# solar_panel_12v.net
KiCad netlist of a schematic drawn in EasyEDA Pro
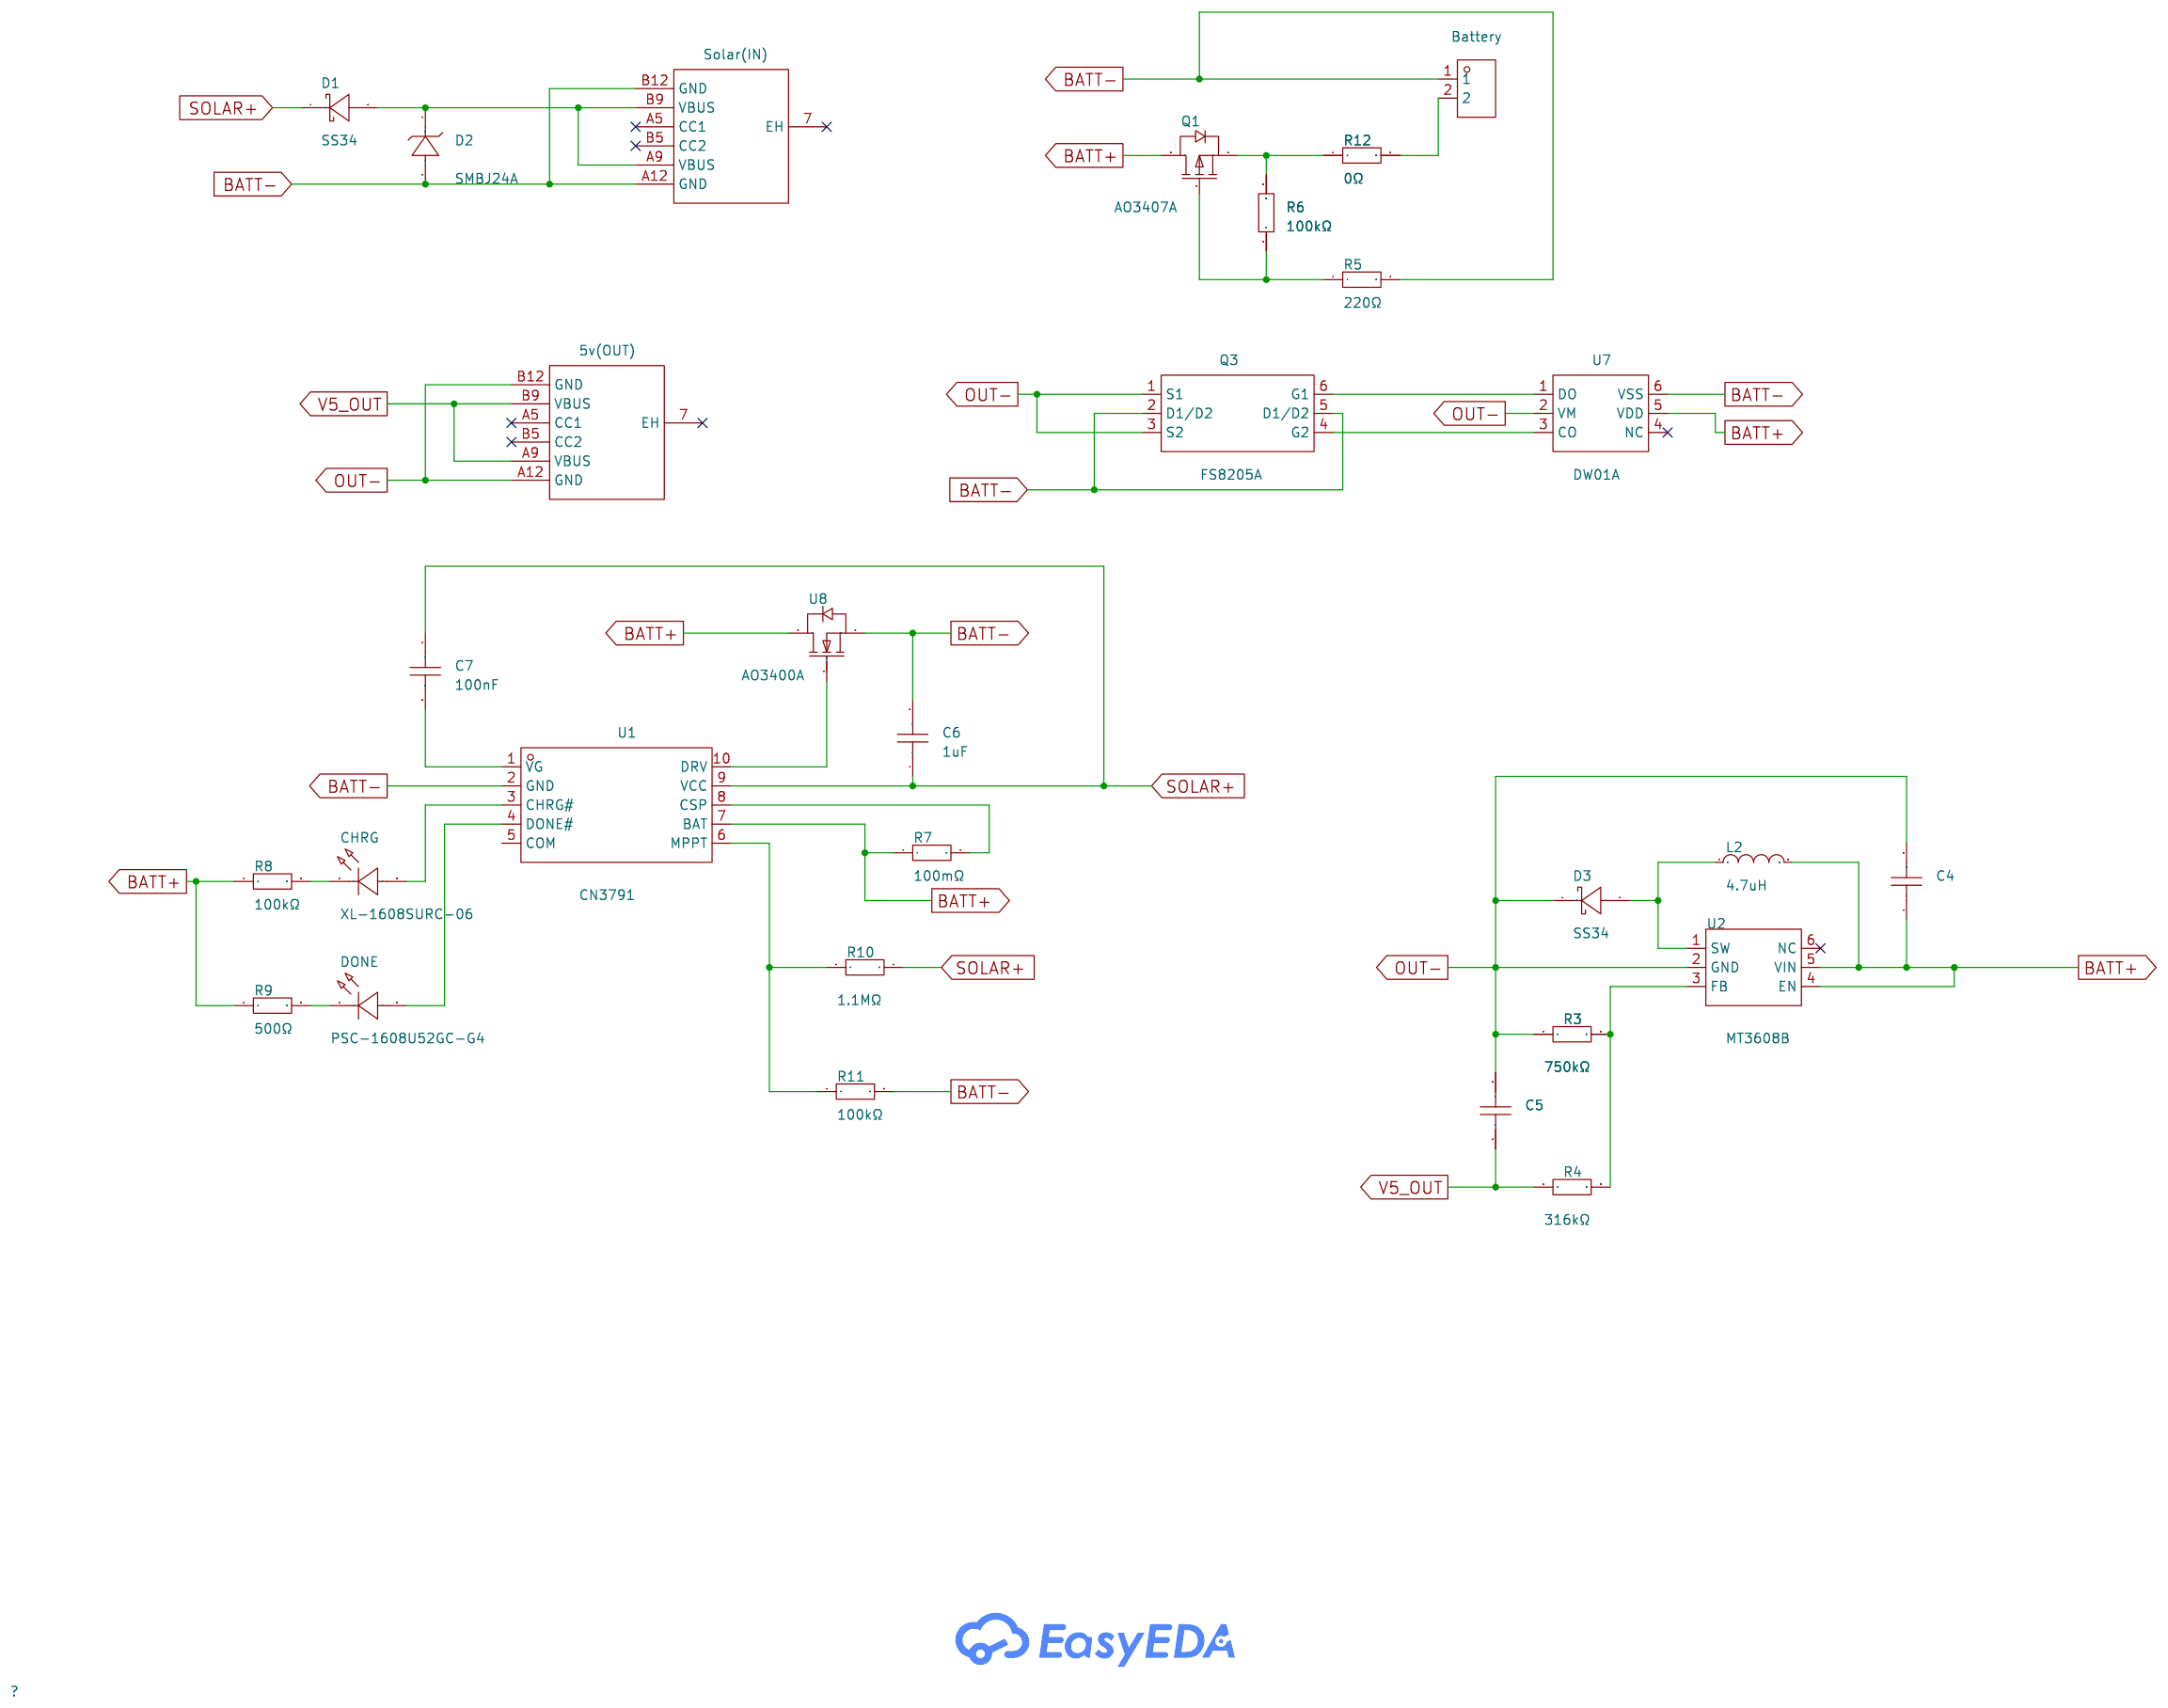
[diagram p0: schematic sheet]

(export (version "E")
  (design (tool "Eeschema 10.0.6"))
  (components
    (comp (ref "5v(OUT)")
      (value "TYPE-C 6P")
      (footprint "easyedapro:TYPE-C-SMD_TYPE-C-6P_1")
      (fields (field (name "Manufacturer") "SHOU HAN(首韩)"))
      (libsource (lib "easyedapro") (part "TYPE-C 6P"))
    )
    (comp (ref "Battery") (value "S2B-PH-SM4-TB(LF)(SN)") (libsource (lib "easyedapro") (part "B2B-PH-KL")))
    (comp (ref "C4")
      (value "10uF")
      (footprint "easyedapro:C0603")
      (description "Capacitance:10uF Tolerance:±20% Tolerance:±20% Voltage Rating:6.3V Temperature Coefficient:X5R")
      (fields (field (name "Manufacturer Part") "C0603B106M007T") (field (name "Manufacturer") "IHHEC(禾伸堂)"))
      (libsource (lib "easyedapro") (part "CAP"))
    )
    (comp (ref "C5")
      (value "10uF")
      (footprint "easyedapro:C0603")
      (description "Capacitance:10uF Tolerance:±20% Tolerance:±20% Voltage Rating:6.3V Temperature Coefficient:X5R")
      (fields (field (name "Manufacturer Part") "C0603B106M007T") (field (name "Manufacturer") "IHHEC(禾伸堂)"))
      (libsource (lib "easyedapro") (part "CAP"))
    )
    (comp (ref "C6")
      (value "1uF")
      (footprint "easyedapro:C0603")
      (description "Capacitance:1uF Tolerance:±10% Tolerance:±10% Voltage Rating:25V Temperature Coefficient:X7R")
      (fields (field (name "Manufacturer Part") "C0603X105K025T") (field (name "Manufacturer") "IHHEC(禾伸堂)"))
      (libsource (lib "easyedapro") (part "CAP"))
    )
    (comp (ref "C7")
      (value "100nF")
      (footprint "easyedapro:C0603")
      (description "Capacitance:100nF Tolerance:±10% Tolerance:±10% Voltage Rating:100V Temperature Coefficient:X7R")
      (fields
        (field (name "Manufacturer Part") "CC0603KRX7R0BB104")
        (field (name "Manufacturer") "YAGEO(国巨)")
      )
      (libsource (lib "easyedapro") (part "CAP"))
    )
    (comp (ref "CHRG")
      (value "XL-1608SURC-06")
      (footprint "easyedapro:LED0603-RD_RED")
      (fields (field (name "Manufacturer") "XINGLIGHT(成兴光)"))
      (libsource (lib "easyedapro") (part "XL-1608SURC-06"))
    )
    (comp (ref "D1")
      (value "SS34")
      (footprint "easyedapro:SMA_L4.3-W2.6-LS5.1-RD")
      (fields (field (name "Manufacturer") "Hangyu(航昱微)"))
      (libsource (lib "easyedapro") (part "SS34_C52023881"))
    )
    (comp (ref "D2")
      (value "SMBJ24A")
      (footprint "easyedapro:SMB_L4.6-W3.6-LS5.3-RD")
      (fields (field (name "Manufacturer") "KUU"))
      (libsource (lib "easyedapro") (part "SMBJ24A_C5343588"))
    )
    (comp (ref "D3")
      (value "SS34")
      (footprint "easyedapro:SMA_L4.3-W2.6-LS5.1-RD")
      (fields (field (name "Manufacturer") "Hangyu(航昱微)"))
      (libsource (lib "easyedapro") (part "SS34_C52023881"))
    )
    (comp (ref "DONE")
      (value "PSC-1608U52GC-G4")
      (footprint "easyedapro:LED0603-RD_GREEN")
      (fields (field (name "Manufacturer") "HONGLITRONIC(鸿利光电)"))
      (libsource (lib "easyedapro") (part "PSC-1608U52GC-G4"))
    )
    (comp (ref "L2")
      (value "4.7uH")
      (footprint "easyedapro:L0805")
      (fields
        (field (name "Manufacturer Part") "CPY201209T-4R7M-NP")
        (field (name "Manufacturer") "Chilisin(奇力新)")
      )
      (libsource (lib "easyedapro") (part "CPY201209T-4R7M-NP"))
    )
    (comp (ref "Q1")
      (value "AO3407A")
      (footprint "easyedapro:SOT-23_L2.9-W1.3-P1.90-LS2.4-BR")
      (fields (field (name "Manufacturer") "UMW(友台半导体)"))
      (libsource (lib "easyedapro") (part "AO3407A_C347478"))
    )
    (comp (ref "Q3")
      (value "FS8205A")
      (footprint "easyedapro:SOT-23-6_L2.9-W1.6-P0.95-LS2.8-BR")
      (fields (field (name "Manufacturer") "FUXINSEMI(富芯森美)"))
      (libsource (lib "easyedapro") (part "FS8205A_C908265"))
    )
    (comp (ref "R3")
      (value "750kΩ")
      (footprint "easyedapro:R0603")
      (fields (field (name "Manufacturer Part") "CR0603FA7503G") (field (name "Manufacturer") "LIZ(丽智电子)"))
      (libsource (lib "easyedapro") (part "Res"))
    )
    (comp (ref "R4")
      (value "316kΩ")
      (footprint "easyedapro:R0603")
      (fields (field (name "Manufacturer Part") "FRC0603F3163TS") (field (name "Manufacturer") "FOJAN(富捷)"))
      (libsource (lib "easyedapro") (part "Res"))
    )
    (comp (ref "R5")
      (value "220Ω")
      (footprint "easyedapro:R0603")
      (fields (field (name "Manufacturer Part") "SCR0603J220R") (field (name "Manufacturer") "VO(翔胜)"))
      (libsource (lib "easyedapro") (part "Res"))
    )
    (comp (ref "R6")
      (value "100kΩ")
      (footprint "easyedapro:R0603")
      (fields (field (name "Manufacturer Part") "FCR0603F100K") (field (name "Manufacturer") "VO(翔胜)"))
      (libsource (lib "easyedapro") (part "Res"))
    )
    (comp (ref "R7")
      (value "100mΩ")
      (footprint "easyedapro:R0603")
      (fields (field (name "Manufacturer Part") "FRM121WFR100TM") (field (name "Manufacturer") "FOJAN(富捷)"))
      (libsource (lib "easyedapro") (part "Res"))
    )
    (comp (ref "R8")
      (value "100kΩ")
      (footprint "easyedapro:R0603")
      (fields (field (name "Manufacturer Part") "FCR0603F100K") (field (name "Manufacturer") "VO(翔胜)"))
      (libsource (lib "easyedapro") (part "Res"))
    )
    (comp (ref "R9")
      (value "500Ω")
      (footprint "easyedapro:R0603")
      (fields (field (name "Manufacturer Part") "ARG05FTC5000") (field (name "Manufacturer") "Viking(光颉)"))
      (libsource (lib "easyedapro") (part "Res"))
    )
    (comp (ref "R10")
      (value "1.1MΩ")
      (footprint "easyedapro:R0603")
      (fields (field (name "Manufacturer Part") "FRC0603J115TS") (field (name "Manufacturer") "FOJAN(富捷)"))
      (libsource (lib "easyedapro") (part "Res"))
    )
    (comp (ref "R11")
      (value "100kΩ")
      (footprint "easyedapro:R0603")
      (fields
        (field (name "Manufacturer Part") "CR0603J100KP05Z")
        (field (name "Manufacturer") "EVER OHMS(天二科技)")
      )
      (libsource (lib "easyedapro") (part "Res"))
    )
    (comp (ref "R12")
      (value "0Ω")
      (footprint "easyedapro:R0603")
      (fields (field (name "Manufacturer Part") "FRC1812P000 TS") (field (name "Manufacturer") "FOJAN(富捷)"))
      (libsource (lib "easyedapro") (part "Res"))
    )
    (comp (ref "Solar(IN)")
      (value "TYPE-C 6P")
      (footprint "easyedapro:TYPE-C-SMD_TYPE-C-6P_1")
      (fields (field (name "Manufacturer") "SHOU HAN(首韩)"))
      (libsource (lib "easyedapro") (part "TYPE-C 6P"))
    )
    (comp (ref "U1")
      (value "CN3791")
      (footprint "easyedapro:SSOP-10_L4.9-W3.9-P1.00-LS6.0-BL")
      (fields (field (name "Manufacturer") "CONSONANCE(上海如韵)"))
      (libsource (lib "easyedapro") (part "CN3791"))
    )
    (comp (ref "U2")
      (value "MT3608B")
      (footprint "easyedapro:SOT-23-6_L2.9-W1.6-P0.95-LS2.8-BR")
      (fields (field (name "Manufacturer") "西安航天民芯"))
      (libsource (lib "easyedapro") (part "MT3608B"))
    )
    (comp (ref "U7")
      (value "DW01A")
      (footprint "easyedapro:SOT-23-6_L2.9-W1.6-P0.95-LS2.9-BL")
      (fields (field (name "Manufacturer") "Slkor(萨科微)"))
      (libsource (lib "easyedapro") (part "DW01A_C42380662"))
    )
    (comp (ref "U8")
      (value "AO3400A")
      (footprint "easyedapro:SOT-23-3_L2.9-W1.3-P1.90-LS2.4-BR")
      (fields (field (name "Manufacturer") "YONGYUTAI(永裕泰)"))
      (libsource (lib "easyedapro") (part "AO3400A_C49195711"))
    )
  )
  (nets
    (net (code "1") (name "BATT+") (class "Default")
      (node (ref "C4") (pin "1") (pinfunction "1_1") (pintype "input"))
      (node (ref "L2") (pin "2") (pinfunction "2_2") (pintype "unspecified"))
      (node (ref "Q1") (pin "3") (pinfunction "D_3") (pintype "unspecified"))
      (node (ref "R7") (pin "1") (pinfunction "1_1") (pintype "input"))
      (node (ref "R8") (pin "1") (pinfunction "1_1") (pintype "input"))
      (node (ref "R9") (pin "1") (pinfunction "1_1") (pintype "input"))
      (node (ref "U1") (pin "7") (pinfunction "BAT_7") (pintype "unspecified"))
      (node (ref "U2") (pin "4") (pinfunction "EN_4") (pintype "unspecified"))
      (node (ref "U2") (pin "5") (pinfunction "VIN_5") (pintype "unspecified"))
      (node (ref "U7") (pin "5") (pinfunction "VDD_5") (pintype "unspecified"))
      (node (ref "U8") (pin "3") (pinfunction "D_3") (pintype "unspecified"))
    )
    (net (code "2") (name "BATT-") (class "Default")
      (node (ref "Battery") (pin "1") (pinfunction "1_1") (pintype "unspecified"))
      (node (ref "C6") (pin "2") (pinfunction "2_2") (pintype "input"))
      (node (ref "D2") (pin "2") (pinfunction "A_2") (pintype "unspecified"))
      (node (ref "Q3") (pin "2") (pinfunction "D1/D2_2") (pintype "unspecified"))
      (node (ref "Q3") (pin "5") (pinfunction "D1/D2_5") (pintype "unspecified"))
      (node (ref "R11") (pin "2") (pinfunction "2_2") (pintype "input"))
      (node (ref "R5") (pin "2") (pinfunction "2_2") (pintype "input"))
      (node (ref "Solar(IN)") (pin "A12") (pinfunction "GND_A12") (pintype "unspecified"))
      (node (ref "Solar(IN)") (pin "B12") (pinfunction "GND_B12") (pintype "unspecified"))
      (node (ref "U1") (pin "2") (pinfunction "GND_2") (pintype "unspecified"))
      (node (ref "U7") (pin "6") (pinfunction "VSS_6") (pintype "unspecified"))
      (node (ref "U8") (pin "2") (pinfunction "S_2") (pintype "unspecified"))
    )
    (net (code "3") (name "Net-(Battery-Pad2)") (class "Default")
      (node (ref "Battery") (pin "2") (pinfunction "2_2") (pintype "unspecified"))
      (node (ref "R12") (pin "2") (pinfunction "2_2") (pintype "input"))
    )
    (net (code "4") (name "Net-(CHRG-A)") (class "Default")
      (node (ref "CHRG") (pin "2") (pinfunction "A_2") (pintype "unspecified"))
      (node (ref "U1") (pin "3") (pinfunction "CHRG#_3") (pintype "unspecified"))
    )
    (net (code "5") (name "Net-(CHRG-K)") (class "Default")
      (node (ref "CHRG") (pin "1") (pinfunction "K_1") (pintype "unspecified"))
      (node (ref "R8") (pin "2") (pinfunction "2_2") (pintype "input"))
    )
    (net (code "6") (name "Net-(D1-A)") (class "Default")
      (node (ref "D1") (pin "2") (pinfunction "A_2") (pintype "unspecified"))
      (node (ref "D2") (pin "1") (pinfunction "C_1") (pintype "unspecified"))
      (node (ref "Solar(IN)") (pin "A9") (pinfunction "VBUS_A9") (pintype "unspecified"))
      (node (ref "Solar(IN)") (pin "B9") (pinfunction "VBUS_B9") (pintype "unspecified"))
    )
    (net (code "7") (name "Net-(D3-A)") (class "Default")
      (node (ref "D3") (pin "2") (pinfunction "A_2") (pintype "unspecified"))
      (node (ref "L2") (pin "1") (pinfunction "1_1") (pintype "unspecified"))
      (node (ref "U2") (pin "1") (pinfunction "SW_1") (pintype "unspecified"))
    )
    (net (code "8") (name "Net-(DONE-A)") (class "Default")
      (node (ref "DONE") (pin "2") (pinfunction "A_2") (pintype "unspecified"))
      (node (ref "U1") (pin "4") (pinfunction "DONE#_4") (pintype "unspecified"))
    )
    (net (code "9") (name "Net-(DONE-K)") (class "Default")
      (node (ref "DONE") (pin "1") (pinfunction "K_1") (pintype "unspecified"))
      (node (ref "R9") (pin "2") (pinfunction "2_2") (pintype "input"))
    )
    (net (code "10") (name "Net-(Q1-G)") (class "Default")
      (node (ref "Q1") (pin "1") (pinfunction "G_1") (pintype "unspecified"))
      (node (ref "R5") (pin "1") (pinfunction "1_1") (pintype "input"))
      (node (ref "R6") (pin "1") (pinfunction "1_1") (pintype "input"))
    )
    (net (code "11") (name "Net-(Q1-S)") (class "Default")
      (node (ref "Q1") (pin "2") (pinfunction "S_2") (pintype "unspecified"))
      (node (ref "R12") (pin "1") (pinfunction "1_1") (pintype "input"))
      (node (ref "R6") (pin "2") (pinfunction "2_2") (pintype "input"))
    )
    (net (code "12") (name "Net-(Q3-G1)") (class "Default")
      (node (ref "Q3") (pin "6") (pinfunction "G1_6") (pintype "unspecified"))
      (node (ref "U7") (pin "1") (pinfunction "DO_1") (pintype "unspecified"))
    )
    (net (code "13") (name "Net-(Q3-G2)") (class "Default")
      (node (ref "Q3") (pin "4") (pinfunction "G2_4") (pintype "unspecified"))
      (node (ref "U7") (pin "3") (pinfunction "CO_3") (pintype "unspecified"))
    )
    (net (code "14") (name "Net-(U1-CSP)") (class "Default")
      (node (ref "R7") (pin "2") (pinfunction "2_2") (pintype "input"))
      (node (ref "U1") (pin "8") (pinfunction "CSP_8") (pintype "unspecified"))
    )
    (net (code "15") (name "Net-(U1-DRV)") (class "Default")
      (node (ref "U1") (pin "10") (pinfunction "DRV_10") (pintype "unspecified"))
      (node (ref "U8") (pin "1") (pinfunction "G_1") (pintype "unspecified"))
    )
    (net (code "16") (name "Net-(U1-MPPT)") (class "Default")
      (node (ref "R10") (pin "1") (pinfunction "1_1") (pintype "input"))
      (node (ref "R11") (pin "1") (pinfunction "1_1") (pintype "input"))
      (node (ref "U1") (pin "6") (pinfunction "MPPT_6") (pintype "unspecified"))
    )
    (net (code "17") (name "Net-(U1-VG)") (class "Default")
      (node (ref "C7") (pin "2") (pinfunction "2_2") (pintype "input"))
      (node (ref "U1") (pin "1") (pinfunction "VG_1") (pintype "unspecified"))
    )
    (net (code "18") (name "Net-(U2-FB)") (class "Default")
      (node (ref "R3") (pin "2") (pinfunction "2_2") (pintype "input"))
      (node (ref "R4") (pin "2") (pinfunction "2_2") (pintype "input"))
      (node (ref "U2") (pin "3") (pinfunction "FB_3") (pintype "unspecified"))
    )
    (net (code "19") (name "OUT-") (class "Default")
      (node (ref "5v(OUT)") (pin "A12") (pinfunction "GND_A12") (pintype "unspecified"))
      (node (ref "5v(OUT)") (pin "B12") (pinfunction "GND_B12") (pintype "unspecified"))
      (node (ref "C4") (pin "2") (pinfunction "2_2") (pintype "input"))
      (node (ref "C5") (pin "2") (pinfunction "2_2") (pintype "input"))
      (node (ref "D3") (pin "1") (pinfunction "C_1") (pintype "unspecified"))
      (node (ref "Q3") (pin "1") (pinfunction "S1_1") (pintype "unspecified"))
      (node (ref "Q3") (pin "3") (pinfunction "S2_3") (pintype "unspecified"))
      (node (ref "R3") (pin "1") (pinfunction "1_1") (pintype "input"))
      (node (ref "U2") (pin "2") (pinfunction "GND_2") (pintype "unspecified"))
      (node (ref "U7") (pin "2") (pinfunction "VM_2") (pintype "unspecified"))
    )
    (net (code "20") (name "SOLAR+") (class "Default")
      (node (ref "C6") (pin "1") (pinfunction "1_1") (pintype "input"))
      (node (ref "C7") (pin "1") (pinfunction "1_1") (pintype "input"))
      (node (ref "D1") (pin "1") (pinfunction "C_1") (pintype "unspecified"))
      (node (ref "R10") (pin "2") (pinfunction "2_2") (pintype "input"))
      (node (ref "U1") (pin "9") (pinfunction "VCC_9") (pintype "unspecified"))
    )
    (net (code "21") (name "V5_OUT") (class "Default")
      (node (ref "5v(OUT)") (pin "A9") (pinfunction "VBUS_A9") (pintype "unspecified"))
      (node (ref "5v(OUT)") (pin "B9") (pinfunction "VBUS_B9") (pintype "unspecified"))
      (node (ref "C5") (pin "1") (pinfunction "1_1") (pintype "input"))
      (node (ref "R4") (pin "1") (pinfunction "1_1") (pintype "input"))
    )
    (net (code "22") (name "unconnected-(5v(OUT)-CC1-PadA5)") (class "Default")
      (node (ref "5v(OUT)") (pin "A5") (pinfunction "CC1_A5") (pintype "unspecified+no_connect"))
    )
    (net (code "23") (name "unconnected-(5v(OUT)-CC2-PadB5)") (class "Default")
      (node (ref "5v(OUT)") (pin "B5") (pinfunction "CC2_B5") (pintype "unspecified+no_connect"))
    )
    (net (code "24") (name "unconnected-(5v(OUT)-EH-Pad7)") (class "Default")
      (node (ref "5v(OUT)") (pin "7") (pinfunction "EH_7") (pintype "unspecified+no_connect"))
    )
    (net (code "25") (name "unconnected-(Solar(IN)-CC1-PadA5)") (class "Default")
      (node (ref "Solar(IN)") (pin "A5") (pinfunction "CC1_A5") (pintype "unspecified+no_connect"))
    )
    (net (code "26") (name "unconnected-(Solar(IN)-CC2-PadB5)") (class "Default")
      (node (ref "Solar(IN)") (pin "B5") (pinfunction "CC2_B5") (pintype "unspecified+no_connect"))
    )
    (net (code "27") (name "unconnected-(Solar(IN)-EH-Pad7)") (class "Default")
      (node (ref "Solar(IN)") (pin "7") (pinfunction "EH_7") (pintype "unspecified+no_connect"))
    )
    (net (code "28") (name "unconnected-(U1-COM-Pad5)") (class "Default")
      (node (ref "U1") (pin "5") (pinfunction "COM_5") (pintype "unspecified"))
    )
    (net (code "29") (name "unconnected-(U2-NC-Pad6)") (class "Default")
      (node (ref "U2") (pin "6") (pinfunction "NC_6") (pintype "unspecified+no_connect"))
    )
    (net (code "30") (name "unconnected-(U7-NC-Pad4)") (class "Default")
      (node (ref "U7") (pin "4") (pinfunction "NC_4") (pintype "unspecified+no_connect"))
    )
  )
)
